# 5v-to3.net
KiCad netlist of a schematic drawn in EAGLE
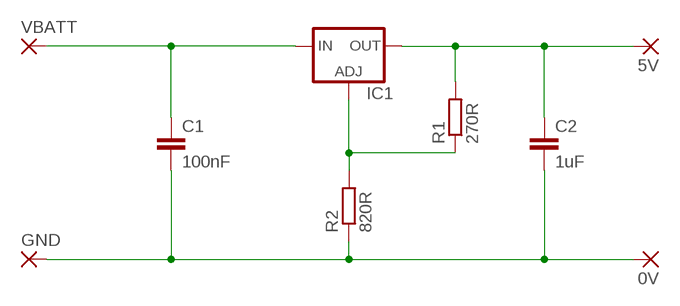
[diagram p0: schematic, sheet 1]

(export (version "E")
  (design (tool "Eeschema 10.0.6"))
  (components
    (comp (ref "0V")
      (value "WIREPAD4,16O1,6")
      (footprint "eagle-import:4,16O1,6")
      (libsource (lib "eagle-import") (part "WIREPAD4,16O1,6"))
    )
    (comp (ref "5V")
      (value "WIREPAD4,16O1,6")
      (footprint "eagle-import:4,16O1,6")
      (libsource (lib "eagle-import") (part "WIREPAD4,16O1,6"))
    )
    (comp (ref "C1")
      (value "100nF")
      (footprint "eagle-import:C050-024X044")
      (libsource (lib "eagle-import") (part "C-EU050-024X044"))
    )
    (comp (ref "C2")
      (value "1uF")
      (footprint "eagle-import:C050-024X044")
      (libsource (lib "eagle-import") (part "C-EU050-024X044"))
    )
    (comp (ref "GND")
      (value "WIREPAD4,16O1,6")
      (footprint "eagle-import:4,16O1,6")
      (libsource (lib "eagle-import") (part "WIREPAD4,16O1,6"))
    )
    (comp (ref "IC1")
      (value "LM138-TO3")
      (footprint "eagle-import:TO3-K02")
      (libsource (lib "eagle-import") (part "LM138-TO3"))
    )
    (comp (ref "R1")
      (value "270R")
      (footprint "eagle-import:0207_7")
      (libsource (lib "eagle-import") (part "R-EU_0207/7"))
    )
    (comp (ref "R2")
      (value "820R")
      (footprint "eagle-import:0207_7")
      (libsource (lib "eagle-import") (part "R-EU_0207/7"))
    )
    (comp (ref "VBATT")
      (value "WIREPAD4,16O1,6")
      (footprint "eagle-import:4,16O1,6")
      (libsource (lib "eagle-import") (part "WIREPAD4,16O1,6"))
    )
  )
  (nets
    (net (code "1") (name "Net-(0V-P)") (class "Default")
      (node (ref "0V") (pin "1") (pinfunction "P_1") (pintype "passive"))
      (node (ref "C1") (pin "2") (pinfunction "2_2") (pintype "passive"))
      (node (ref "C2") (pin "2") (pinfunction "2_2") (pintype "passive"))
      (node (ref "GND") (pin "1") (pinfunction "P_1") (pintype "passive"))
      (node (ref "R2") (pin "1") (pinfunction "1_1") (pintype "passive"))
    )
    (net (code "2") (name "Net-(5V-P)") (class "Default")
      (node (ref "5V") (pin "1") (pinfunction "P_1") (pintype "passive"))
      (node (ref "C2") (pin "1") (pinfunction "1_1") (pintype "passive"))
      (node (ref "IC1") (pin "3") (pinfunction "OUT_3") (pintype "passive"))
      (node (ref "R1") (pin "2") (pinfunction "2_2") (pintype "passive"))
    )
    (net (code "3") (name "Net-(IC1-ADJ)") (class "Default")
      (node (ref "IC1") (pin "2") (pinfunction "ADJ_2") (pintype "input"))
      (node (ref "R1") (pin "1") (pinfunction "1_1") (pintype "passive"))
      (node (ref "R2") (pin "2") (pinfunction "2_2") (pintype "passive"))
    )
    (net (code "4") (name "Net-(IC1-IN)") (class "Default")
      (node (ref "C1") (pin "1") (pinfunction "1_1") (pintype "passive"))
      (node (ref "IC1") (pin "1") (pinfunction "IN_1") (pintype "input"))
      (node (ref "VBATT") (pin "1") (pinfunction "P_1") (pintype "passive"))
    )
  )
)
